# psu_board.net
KiCad netlist of a schematic drawn in EAGLE
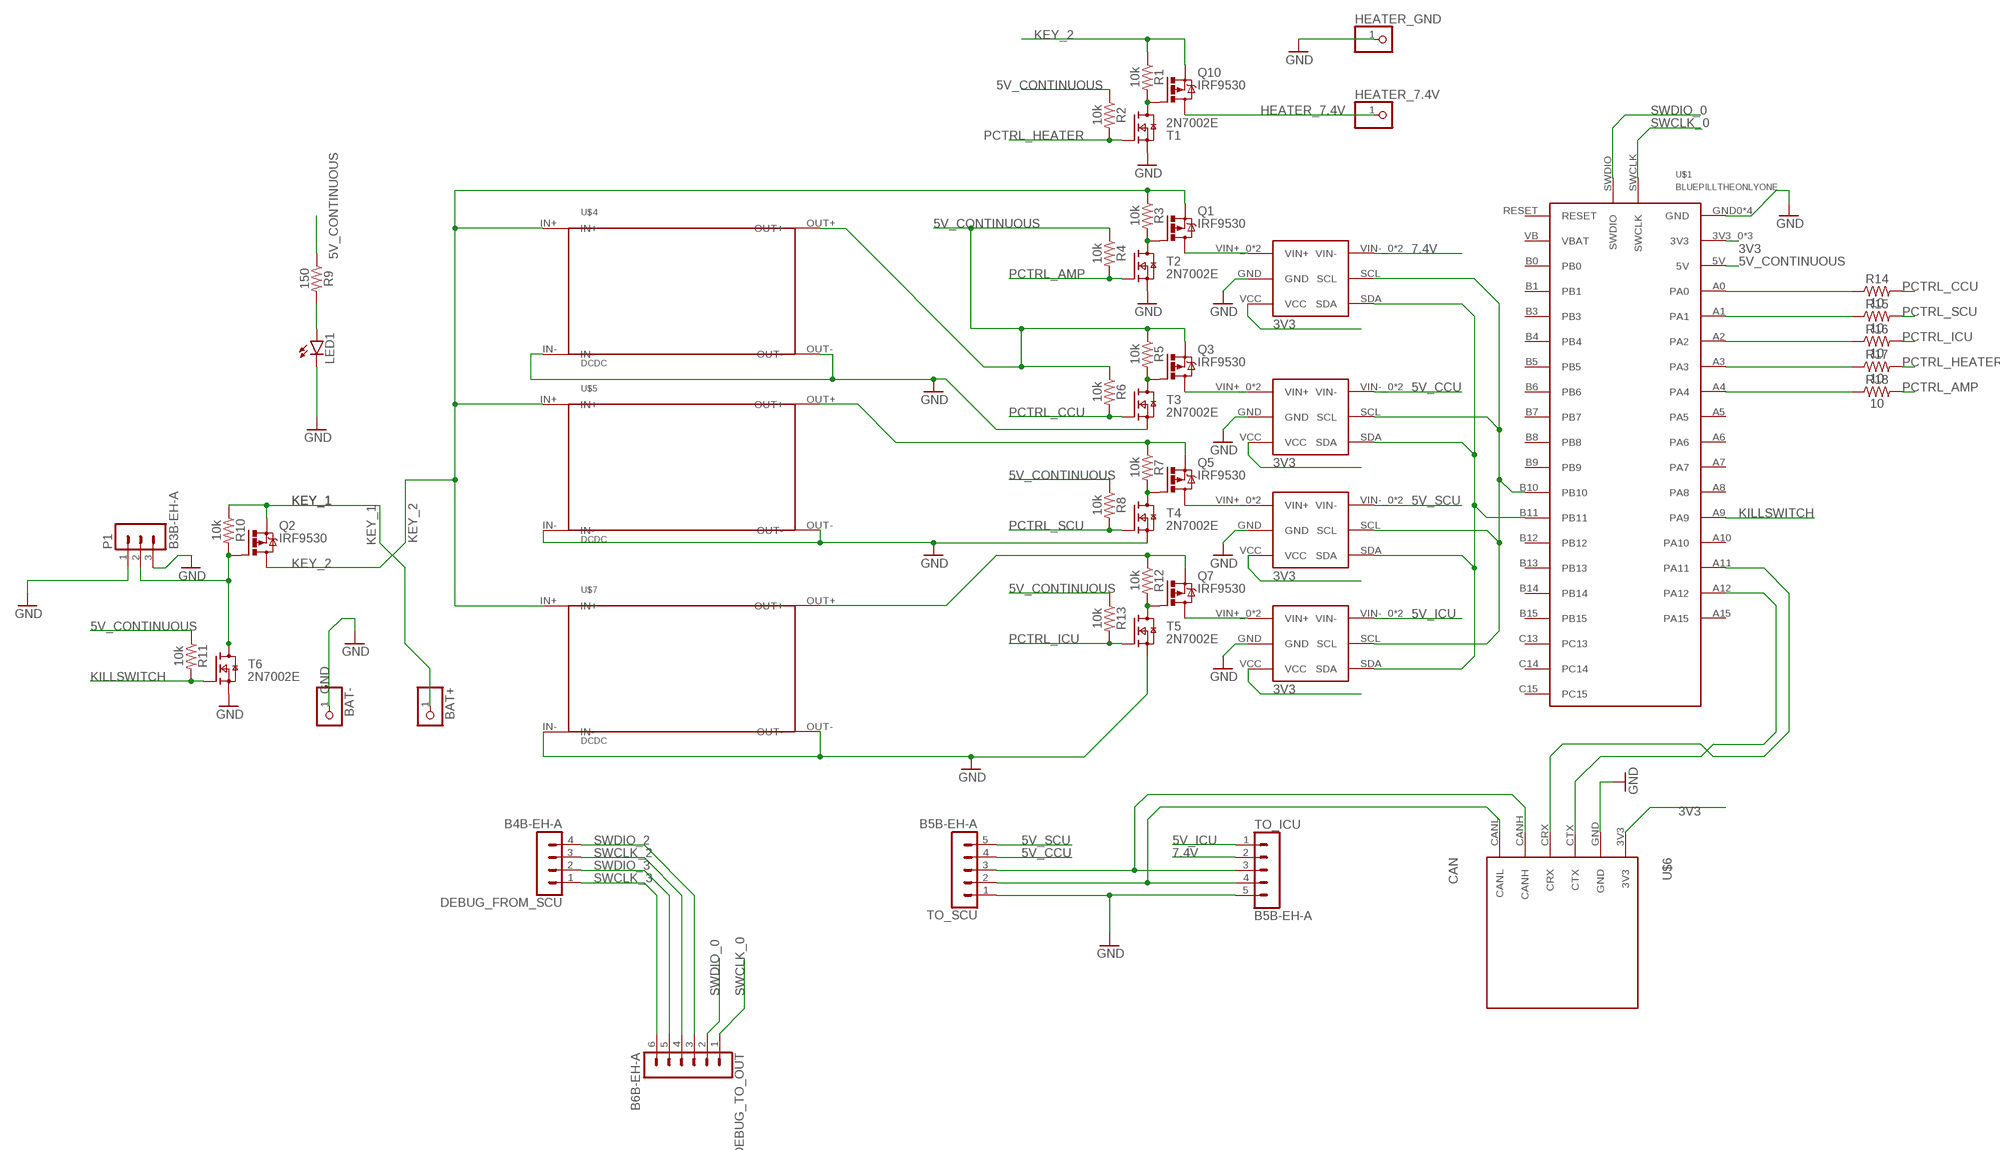
[diagram p0: schematic, sheet 1]

(export (version "E")
  (design (tool "Eeschema 10.0.6"))
  (components
    (comp (ref "BAT+")
      (value "PINHD-1X1")
      (footprint "eagle-import:1X01")
      (libsource (lib "eagle-import") (part "PINHD-1X1"))
    )
    (comp (ref "BAT-")
      (value "PINHD-1X1")
      (footprint "eagle-import:1X01")
      (libsource (lib "eagle-import") (part "PINHD-1X1"))
    )
    (comp (ref "DEBUG_FROM_SCU")
      (value "B4B-EH-A")
      (footprint "eagle-import:B4B-EH-A")
      (libsource (lib "eagle-import") (part "B4B-EH-A"))
    )
    (comp (ref "DEBUG_TO_OUT")
      (value "B6B-EH-A")
      (footprint "eagle-import:B6B-EH-A")
      (libsource (lib "eagle-import") (part "B6B-EH-A"))
    )
    (comp (ref "HEATER_7.4V")
      (value "PINHD-1X1")
      (footprint "eagle-import:1X01")
      (libsource (lib "eagle-import") (part "PINHD-1X1"))
    )
    (comp (ref "HEATER_GND")
      (value "PINHD-1X1")
      (footprint "eagle-import:1X01")
      (libsource (lib "eagle-import") (part "PINHD-1X1"))
    )
    (comp (ref "LED1")
      (value "LED5MM")
      (footprint "eagle-import:LED5MM")
      (libsource (lib "eagle-import") (part "LED5MM"))
    )
    (comp (ref "P1")
      (value "B3B-EH-A")
      (footprint "eagle-import:B3B-EH-A")
      (libsource (lib "eagle-import") (part "B3B-EH-A"))
    )
    (comp (ref "Q1")
      (value "IRF9530")
      (footprint "eagle-import:TO220BV")
      (libsource (lib "eagle-import") (part "IRF9530"))
    )
    (comp (ref "Q2")
      (value "IRF9530")
      (footprint "eagle-import:TO220BV")
      (libsource (lib "eagle-import") (part "IRF9530"))
    )
    (comp (ref "Q3")
      (value "IRF9530")
      (footprint "eagle-import:TO220BV")
      (libsource (lib "eagle-import") (part "IRF9530"))
    )
    (comp (ref "Q5")
      (value "IRF9530")
      (footprint "eagle-import:TO220BV")
      (libsource (lib "eagle-import") (part "IRF9530"))
    )
    (comp (ref "Q7")
      (value "IRF9530")
      (footprint "eagle-import:TO220BV")
      (libsource (lib "eagle-import") (part "IRF9530"))
    )
    (comp (ref "Q10")
      (value "IRF9530")
      (footprint "eagle-import:TO220BV")
      (libsource (lib "eagle-import") (part "IRF9530"))
    )
    (comp (ref "R1")
      (value "10k")
      (footprint "eagle-import:AXIAL-0.3")
      (libsource (lib "eagle-import") (part "RESISTORAXIAL-0.3"))
    )
    (comp (ref "R2")
      (value "10k")
      (footprint "eagle-import:AXIAL-0.3")
      (libsource (lib "eagle-import") (part "RESISTORAXIAL-0.3"))
    )
    (comp (ref "R3")
      (value "10k")
      (footprint "eagle-import:AXIAL-0.3")
      (libsource (lib "eagle-import") (part "RESISTORAXIAL-0.3"))
    )
    (comp (ref "R4")
      (value "10k")
      (footprint "eagle-import:AXIAL-0.3")
      (libsource (lib "eagle-import") (part "RESISTORAXIAL-0.3"))
    )
    (comp (ref "R5")
      (value "10k")
      (footprint "eagle-import:AXIAL-0.3")
      (libsource (lib "eagle-import") (part "RESISTORAXIAL-0.3"))
    )
    (comp (ref "R6")
      (value "10k")
      (footprint "eagle-import:AXIAL-0.3")
      (libsource (lib "eagle-import") (part "RESISTORAXIAL-0.3"))
    )
    (comp (ref "R7")
      (value "10k")
      (footprint "eagle-import:AXIAL-0.3")
      (libsource (lib "eagle-import") (part "RESISTORAXIAL-0.3"))
    )
    (comp (ref "R8")
      (value "10k")
      (footprint "eagle-import:AXIAL-0.3")
      (libsource (lib "eagle-import") (part "RESISTORAXIAL-0.3"))
    )
    (comp (ref "R9")
      (value "150")
      (footprint "eagle-import:AXIAL-0.3")
      (libsource (lib "eagle-import") (part "RESISTORAXIAL-0.3"))
    )
    (comp (ref "R10")
      (value "10k")
      (footprint "eagle-import:AXIAL-0.3")
      (libsource (lib "eagle-import") (part "RESISTORAXIAL-0.3"))
    )
    (comp (ref "R11")
      (value "10k")
      (footprint "eagle-import:AXIAL-0.3")
      (libsource (lib "eagle-import") (part "RESISTORAXIAL-0.3"))
    )
    (comp (ref "R12")
      (value "10k")
      (footprint "eagle-import:AXIAL-0.3")
      (libsource (lib "eagle-import") (part "RESISTORAXIAL-0.3"))
    )
    (comp (ref "R13")
      (value "10k")
      (footprint "eagle-import:AXIAL-0.3")
      (libsource (lib "eagle-import") (part "RESISTORAXIAL-0.3"))
    )
    (comp (ref "R14")
      (value "10")
      (footprint "eagle-import:AXIAL-0.3")
      (libsource (lib "eagle-import") (part "RESISTORAXIAL-0.3"))
    )
    (comp (ref "R15")
      (value "10")
      (footprint "eagle-import:AXIAL-0.3")
      (libsource (lib "eagle-import") (part "RESISTORAXIAL-0.3"))
    )
    (comp (ref "R16")
      (value "10")
      (footprint "eagle-import:AXIAL-0.3")
      (libsource (lib "eagle-import") (part "RESISTORAXIAL-0.3"))
    )
    (comp (ref "R17")
      (value "10")
      (footprint "eagle-import:AXIAL-0.3")
      (libsource (lib "eagle-import") (part "RESISTORAXIAL-0.3"))
    )
    (comp (ref "R18")
      (value "10")
      (footprint "eagle-import:AXIAL-0.3")
      (libsource (lib "eagle-import") (part "RESISTORAXIAL-0.3"))
    )
    (comp (ref "T1")
      (value "2N7002E")
      (footprint "eagle-import:SOT23")
      (libsource (lib "eagle-import") (part "2N7002E"))
    )
    (comp (ref "T2")
      (value "2N7002E")
      (footprint "eagle-import:SOT23")
      (libsource (lib "eagle-import") (part "2N7002E"))
    )
    (comp (ref "T3")
      (value "2N7002E")
      (footprint "eagle-import:SOT23")
      (libsource (lib "eagle-import") (part "2N7002E"))
    )
    (comp (ref "T4")
      (value "2N7002E")
      (footprint "eagle-import:SOT23")
      (libsource (lib "eagle-import") (part "2N7002E"))
    )
    (comp (ref "T5")
      (value "2N7002E")
      (footprint "eagle-import:SOT23")
      (libsource (lib "eagle-import") (part "2N7002E"))
    )
    (comp (ref "T6")
      (value "2N7002E")
      (footprint "eagle-import:SOT23")
      (libsource (lib "eagle-import") (part "2N7002E"))
    )
    (comp (ref "TO_ICU")
      (value "B5B-EH-A")
      (footprint "eagle-import:B5B-EH-A")
      (libsource (lib "eagle-import") (part "B5B-EH-A"))
    )
    (comp (ref "TO_SCU")
      (value "B5B-EH-A")
      (footprint "eagle-import:B5B-EH-A")
      (libsource (lib "eagle-import") (part "B5B-EH-A"))
    )
    (comp (ref "U$1")
      (value "BLUEPILLTHEONLYONE")
      (footprint "eagle-import:BLUEPIL")
      (libsource (lib "eagle-import") (part "BLUEPILLTHEONLYONE"))
    )
    (comp (ref "U$2")
      (value "INA")
      (footprint "eagle-import:INA")
      (libsource (lib "eagle-import") (part "INA"))
    )
    (comp (ref "U$3")
      (value "INA")
      (footprint "eagle-import:INA")
      (libsource (lib "eagle-import") (part "INA"))
    )
    (comp (ref "U$4")
      (value "DCDC")
      (footprint "eagle-import:DCDC")
      (libsource (lib "eagle-import") (part "DCDC"))
    )
    (comp (ref "U$5")
      (value "DCDC")
      (footprint "eagle-import:DCDC")
      (libsource (lib "eagle-import") (part "DCDC"))
    )
    (comp (ref "U$6")
      (value "CAN")
      (footprint "eagle-import:CAN")
      (libsource (lib "eagle-import") (part "CAN"))
    )
    (comp (ref "U$7")
      (value "DCDC")
      (footprint "eagle-import:DCDC")
      (libsource (lib "eagle-import") (part "DCDC"))
    )
    (comp (ref "U$8")
      (value "INA")
      (footprint "eagle-import:INA")
      (libsource (lib "eagle-import") (part "INA"))
    )
    (comp (ref "U$9")
      (value "INA")
      (footprint "eagle-import:INA")
      (libsource (lib "eagle-import") (part "INA"))
    )
  )
  (nets
    (net (code "1") (name "/3V3") (class "Default")
      (node (ref "U$1") (pin "3V3_0") (pinfunction "3V3_3V3_0") (pintype "bidirectional"))
      (node (ref "U$1") (pin "3V3_1") (pinfunction "3V3_3V3_1") (pintype "bidirectional"))
      (node (ref "U$1") (pin "3V3_2") (pinfunction "3V3_3V3_2") (pintype "bidirectional"))
      (node (ref "U$2") (pin "VCC") (pinfunction "VCC_VCC") (pintype "bidirectional"))
      (node (ref "U$3") (pin "VCC") (pinfunction "VCC_VCC") (pintype "bidirectional"))
      (node (ref "U$6") (pin "3V3") (pinfunction "3V3_3V3") (pintype "bidirectional"))
      (node (ref "U$8") (pin "VCC") (pinfunction "VCC_VCC") (pintype "bidirectional"))
      (node (ref "U$9") (pin "VCC") (pinfunction "VCC_VCC") (pintype "bidirectional"))
    )
    (net (code "2") (name "/5V_CCU") (class "Default")
      (node (ref "TO_SCU") (pin "4") (pinfunction "4_4") (pintype "passive"))
      (node (ref "U$9") (pin "VIN-_0") (pinfunction "VIN-_VIN-_0") (pintype "bidirectional"))
      (node (ref "U$9") (pin "VIN-_1") (pinfunction "VIN-_VIN-_1") (pintype "bidirectional"))
    )
    (net (code "3") (name "/5V_CONTINUOUS") (class "Default")
      (node (ref "Q3") (pin "S") (pinfunction "S_S") (pintype "passive"))
      (node (ref "R11") (pin "P$1") (pinfunction "1_P$1") (pintype "passive"))
      (node (ref "R13") (pin "P$1") (pinfunction "1_P$1") (pintype "passive"))
      (node (ref "R2") (pin "P$1") (pinfunction "1_P$1") (pintype "passive"))
      (node (ref "R4") (pin "P$1") (pinfunction "1_P$1") (pintype "passive"))
      (node (ref "R5") (pin "P$1") (pinfunction "1_P$1") (pintype "passive"))
      (node (ref "R6") (pin "P$1") (pinfunction "1_P$1") (pintype "passive"))
      (node (ref "R8") (pin "P$1") (pinfunction "1_P$1") (pintype "passive"))
      (node (ref "R9") (pin "P$1") (pinfunction "1_P$1") (pintype "passive"))
      (node (ref "U$1") (pin "5V") (pinfunction "5V_5V") (pintype "bidirectional"))
      (node (ref "U$4") (pin "OUT+") (pinfunction "OUT+_OUT+") (pintype "bidirectional"))
    )
    (net (code "4") (name "/5V_ICU") (class "Default")
      (node (ref "TO_ICU") (pin "1") (pinfunction "1_1") (pintype "passive"))
      (node (ref "U$2") (pin "VIN-_0") (pinfunction "VIN-_VIN-_0") (pintype "bidirectional"))
      (node (ref "U$2") (pin "VIN-_1") (pinfunction "VIN-_VIN-_1") (pintype "bidirectional"))
    )
    (net (code "5") (name "/5V_SCU") (class "Default")
      (node (ref "TO_SCU") (pin "5") (pinfunction "5_5") (pintype "passive"))
      (node (ref "U$8") (pin "VIN-_0") (pinfunction "VIN-_VIN-_0") (pintype "bidirectional"))
      (node (ref "U$8") (pin "VIN-_1") (pinfunction "VIN-_VIN-_1") (pintype "bidirectional"))
    )
    (net (code "6") (name "/7.4V") (class "Default")
      (node (ref "TO_ICU") (pin "2") (pinfunction "2_2") (pintype "passive"))
      (node (ref "U$3") (pin "VIN-_0") (pinfunction "VIN-_VIN-_0") (pintype "bidirectional"))
      (node (ref "U$3") (pin "VIN-_1") (pinfunction "VIN-_VIN-_1") (pintype "bidirectional"))
    )
    (net (code "7") (name "/HEATER_7.4V") (class "Default")
      (node (ref "HEATER_7.4V") (pin "1") (pinfunction "1_1") (pintype "passive"))
      (node (ref "Q10") (pin "D") (pinfunction "D_D") (pintype "passive"))
    )
    (net (code "8") (name "/KEY_1") (class "Default")
      (node (ref "BAT+") (pin "1") (pinfunction "1_1") (pintype "passive"))
      (node (ref "Q2") (pin "S") (pinfunction "S_S") (pintype "passive"))
      (node (ref "R10") (pin "P$1") (pinfunction "1_P$1") (pintype "passive"))
    )
    (net (code "9") (name "/KEY_2") (class "Default")
      (node (ref "Q1") (pin "S") (pinfunction "S_S") (pintype "passive"))
      (node (ref "Q10") (pin "S") (pinfunction "S_S") (pintype "passive"))
      (node (ref "Q2") (pin "D") (pinfunction "D_D") (pintype "passive"))
      (node (ref "R1") (pin "P$1") (pinfunction "1_P$1") (pintype "passive"))
      (node (ref "R3") (pin "P$1") (pinfunction "1_P$1") (pintype "passive"))
      (node (ref "U$4") (pin "IN+") (pinfunction "IN+_IN+") (pintype "bidirectional"))
      (node (ref "U$5") (pin "IN+") (pinfunction "IN+_IN+") (pintype "bidirectional"))
      (node (ref "U$7") (pin "IN+") (pinfunction "IN+_IN+") (pintype "bidirectional"))
    )
    (net (code "10") (name "/KILLSWITCH") (class "Default")
      (node (ref "R11") (pin "P$2") (pinfunction "2_P$2") (pintype "passive"))
      (node (ref "T6") (pin "1") (pinfunction "G_1") (pintype "passive"))
      (node (ref "U$1") (pin "A9") (pinfunction "PA9_A9") (pintype "bidirectional"))
    )
    (net (code "11") (name "/PCTRL_AMP") (class "Default")
      (node (ref "R18") (pin "P$2") (pinfunction "2_P$2") (pintype "passive"))
      (node (ref "R4") (pin "P$2") (pinfunction "2_P$2") (pintype "passive"))
      (node (ref "T2") (pin "1") (pinfunction "G_1") (pintype "passive"))
    )
    (net (code "12") (name "/PCTRL_CCU") (class "Default")
      (node (ref "R14") (pin "P$2") (pinfunction "2_P$2") (pintype "passive"))
      (node (ref "R6") (pin "P$2") (pinfunction "2_P$2") (pintype "passive"))
      (node (ref "T3") (pin "1") (pinfunction "G_1") (pintype "passive"))
    )
    (net (code "13") (name "/PCTRL_HEATER") (class "Default")
      (node (ref "R17") (pin "P$2") (pinfunction "2_P$2") (pintype "passive"))
      (node (ref "R2") (pin "P$2") (pinfunction "2_P$2") (pintype "passive"))
      (node (ref "T1") (pin "1") (pinfunction "G_1") (pintype "passive"))
    )
    (net (code "14") (name "/PCTRL_ICU") (class "Default")
      (node (ref "R13") (pin "P$2") (pinfunction "2_P$2") (pintype "passive"))
      (node (ref "R16") (pin "P$2") (pinfunction "2_P$2") (pintype "passive"))
      (node (ref "T5") (pin "1") (pinfunction "G_1") (pintype "passive"))
    )
    (net (code "15") (name "/PCTRL_SCU") (class "Default")
      (node (ref "R15") (pin "P$2") (pinfunction "2_P$2") (pintype "passive"))
      (node (ref "R8") (pin "P$2") (pinfunction "2_P$2") (pintype "passive"))
      (node (ref "T4") (pin "1") (pinfunction "G_1") (pintype "passive"))
    )
    (net (code "16") (name "/SWCLK_0") (class "Default")
      (node (ref "DEBUG_TO_OUT") (pin "1") (pinfunction "1_1") (pintype "passive"))
      (node (ref "U$1") (pin "SWCLK") (pinfunction "SWCLK_SWCLK") (pintype "bidirectional"))
    )
    (net (code "17") (name "/SWCLK_2") (class "Default")
      (node (ref "DEBUG_FROM_SCU") (pin "3") (pinfunction "3_3") (pintype "passive"))
      (node (ref "DEBUG_TO_OUT") (pin "4") (pinfunction "4_4") (pintype "passive"))
    )
    (net (code "18") (name "/SWCLK_3") (class "Default")
      (node (ref "DEBUG_FROM_SCU") (pin "1") (pinfunction "1_1") (pintype "passive"))
      (node (ref "DEBUG_TO_OUT") (pin "6") (pinfunction "6_6") (pintype "passive"))
    )
    (net (code "19") (name "/SWDIO_0") (class "Default")
      (node (ref "DEBUG_TO_OUT") (pin "2") (pinfunction "2_2") (pintype "passive"))
      (node (ref "U$1") (pin "SWDIO") (pinfunction "SWDIO_SWDIO") (pintype "bidirectional"))
    )
    (net (code "20") (name "/SWDIO_2") (class "Default")
      (node (ref "DEBUG_FROM_SCU") (pin "4") (pinfunction "4_4") (pintype "passive"))
      (node (ref "DEBUG_TO_OUT") (pin "3") (pinfunction "3_3") (pintype "passive"))
    )
    (net (code "21") (name "/SWDIO_3") (class "Default")
      (node (ref "DEBUG_FROM_SCU") (pin "2") (pinfunction "2_2") (pintype "passive"))
      (node (ref "DEBUG_TO_OUT") (pin "5") (pinfunction "5_5") (pintype "passive"))
    )
    (net (code "22") (name "GND") (class "Default")
      (node (ref "BAT-") (pin "1") (pinfunction "1_1") (pintype "passive"))
      (node (ref "HEATER_GND") (pin "1") (pinfunction "1_1") (pintype "passive"))
      (node (ref "LED1") (pin "K") (pinfunction "C_K") (pintype "passive"))
      (node (ref "P1") (pin "1") (pinfunction "1_1") (pintype "passive"))
      (node (ref "P1") (pin "3") (pinfunction "3_3") (pintype "passive"))
      (node (ref "T1") (pin "2") (pinfunction "S_2") (pintype "passive"))
      (node (ref "T2") (pin "2") (pinfunction "S_2") (pintype "passive"))
      (node (ref "T3") (pin "2") (pinfunction "S_2") (pintype "passive"))
      (node (ref "T4") (pin "2") (pinfunction "S_2") (pintype "passive"))
      (node (ref "T5") (pin "2") (pinfunction "S_2") (pintype "passive"))
      (node (ref "T6") (pin "2") (pinfunction "S_2") (pintype "passive"))
      (node (ref "TO_ICU") (pin "5") (pinfunction "5_5") (pintype "passive"))
      (node (ref "TO_SCU") (pin "1") (pinfunction "1_1") (pintype "passive"))
      (node (ref "U$1") (pin "GND0") (pinfunction "GND_GND0") (pintype "bidirectional"))
      (node (ref "U$1") (pin "GND1") (pinfunction "GND_GND1") (pintype "bidirectional"))
      (node (ref "U$1") (pin "GND2") (pinfunction "GND_GND2") (pintype "bidirectional"))
      (node (ref "U$1") (pin "GND3") (pinfunction "GND_GND3") (pintype "bidirectional"))
      (node (ref "U$2") (pin "GND") (pinfunction "GND_GND") (pintype "bidirectional"))
      (node (ref "U$3") (pin "GND") (pinfunction "GND_GND") (pintype "bidirectional"))
      (node (ref "U$4") (pin "IN-") (pinfunction "IN-_IN-") (pintype "bidirectional"))
      (node (ref "U$4") (pin "OUT-") (pinfunction "OUT-_OUT-") (pintype "bidirectional"))
      (node (ref "U$5") (pin "IN-") (pinfunction "IN-_IN-") (pintype "bidirectional"))
      (node (ref "U$5") (pin "OUT-") (pinfunction "OUT-_OUT-") (pintype "bidirectional"))
      (node (ref "U$6") (pin "GND") (pinfunction "GND_GND") (pintype "bidirectional"))
      (node (ref "U$7") (pin "IN-") (pinfunction "IN-_IN-") (pintype "bidirectional"))
      (node (ref "U$7") (pin "OUT-") (pinfunction "OUT-_OUT-") (pintype "bidirectional"))
      (node (ref "U$8") (pin "GND") (pinfunction "GND_GND") (pintype "bidirectional"))
      (node (ref "U$9") (pin "GND") (pinfunction "GND_GND") (pintype "bidirectional"))
    )
    (net (code "23") (name "Net-(Q1-PadD)") (class "Default")
      (node (ref "Q1") (pin "D") (pinfunction "D_D") (pintype "passive"))
      (node (ref "U$3") (pin "VIN+_0") (pinfunction "VIN+_VIN+_0") (pintype "bidirectional"))
      (node (ref "U$3") (pin "VIN+_1") (pinfunction "VIN+_VIN+_1") (pintype "bidirectional"))
    )
    (net (code "24") (name "Net-(Q3-PadD)") (class "Default")
      (node (ref "Q3") (pin "D") (pinfunction "D_D") (pintype "passive"))
      (node (ref "U$9") (pin "VIN+_0") (pinfunction "VIN+_VIN+_0") (pintype "bidirectional"))
      (node (ref "U$9") (pin "VIN+_1") (pinfunction "VIN+_VIN+_1") (pintype "bidirectional"))
    )
    (net (code "25") (name "Net-(Q5-PadD)") (class "Default")
      (node (ref "Q5") (pin "D") (pinfunction "D_D") (pintype "passive"))
      (node (ref "U$8") (pin "VIN+_0") (pinfunction "VIN+_VIN+_0") (pintype "bidirectional"))
      (node (ref "U$8") (pin "VIN+_1") (pinfunction "VIN+_VIN+_1") (pintype "bidirectional"))
    )
    (net (code "26") (name "Net-(Q7-PadD)") (class "Default")
      (node (ref "Q7") (pin "D") (pinfunction "D_D") (pintype "passive"))
      (node (ref "U$2") (pin "VIN+_0") (pinfunction "VIN+_VIN+_0") (pintype "bidirectional"))
      (node (ref "U$2") (pin "VIN+_1") (pinfunction "VIN+_VIN+_1") (pintype "bidirectional"))
    )
    (net (code "27") (name "Net-(R1-2)") (class "Default")
      (node (ref "Q10") (pin "G") (pinfunction "G_G") (pintype "passive"))
      (node (ref "R1") (pin "P$2") (pinfunction "2_P$2") (pintype "passive"))
      (node (ref "T1") (pin "3") (pinfunction "D_3") (pintype "passive"))
    )
    (net (code "28") (name "Net-(R3-2)") (class "Default")
      (node (ref "Q1") (pin "G") (pinfunction "G_G") (pintype "passive"))
      (node (ref "R3") (pin "P$2") (pinfunction "2_P$2") (pintype "passive"))
      (node (ref "T2") (pin "3") (pinfunction "D_3") (pintype "passive"))
    )
    (net (code "29") (name "Net-(R5-2)") (class "Default")
      (node (ref "Q3") (pin "G") (pinfunction "G_G") (pintype "passive"))
      (node (ref "R5") (pin "P$2") (pinfunction "2_P$2") (pintype "passive"))
      (node (ref "T3") (pin "3") (pinfunction "D_3") (pintype "passive"))
    )
    (net (code "30") (name "Net-(R7-1)") (class "Default")
      (node (ref "Q5") (pin "S") (pinfunction "S_S") (pintype "passive"))
      (node (ref "R7") (pin "P$1") (pinfunction "1_P$1") (pintype "passive"))
      (node (ref "U$5") (pin "OUT+") (pinfunction "OUT+_OUT+") (pintype "bidirectional"))
    )
    (net (code "31") (name "Net-(R7-2)") (class "Default")
      (node (ref "Q5") (pin "G") (pinfunction "G_G") (pintype "passive"))
      (node (ref "R7") (pin "P$2") (pinfunction "2_P$2") (pintype "passive"))
      (node (ref "T4") (pin "3") (pinfunction "D_3") (pintype "passive"))
    )
    (net (code "32") (name "Net-(R9-2)") (class "Default")
      (node (ref "LED1") (pin "A") (pinfunction "A_A") (pintype "passive"))
      (node (ref "R9") (pin "P$2") (pinfunction "2_P$2") (pintype "passive"))
    )
    (net (code "33") (name "Net-(R10-2)") (class "Default")
      (node (ref "P1") (pin "2") (pinfunction "2_2") (pintype "passive"))
      (node (ref "Q2") (pin "G") (pinfunction "G_G") (pintype "passive"))
      (node (ref "R10") (pin "P$2") (pinfunction "2_P$2") (pintype "passive"))
      (node (ref "T6") (pin "3") (pinfunction "D_3") (pintype "passive"))
    )
    (net (code "34") (name "Net-(R12-1)") (class "Default")
      (node (ref "Q7") (pin "S") (pinfunction "S_S") (pintype "passive"))
      (node (ref "R12") (pin "P$1") (pinfunction "1_P$1") (pintype "passive"))
      (node (ref "U$7") (pin "OUT+") (pinfunction "OUT+_OUT+") (pintype "bidirectional"))
    )
    (net (code "35") (name "Net-(R12-2)") (class "Default")
      (node (ref "Q7") (pin "G") (pinfunction "G_G") (pintype "passive"))
      (node (ref "R12") (pin "P$2") (pinfunction "2_P$2") (pintype "passive"))
      (node (ref "T5") (pin "3") (pinfunction "D_3") (pintype "passive"))
    )
    (net (code "36") (name "Net-(R14-1)") (class "Default")
      (node (ref "R14") (pin "P$1") (pinfunction "1_P$1") (pintype "passive"))
      (node (ref "U$1") (pin "A0") (pinfunction "PA0_A0") (pintype "bidirectional"))
    )
    (net (code "37") (name "Net-(R15-1)") (class "Default")
      (node (ref "R15") (pin "P$1") (pinfunction "1_P$1") (pintype "passive"))
      (node (ref "U$1") (pin "A1") (pinfunction "PA1_A1") (pintype "bidirectional"))
    )
    (net (code "38") (name "Net-(R16-1)") (class "Default")
      (node (ref "R16") (pin "P$1") (pinfunction "1_P$1") (pintype "passive"))
      (node (ref "U$1") (pin "A2") (pinfunction "PA2_A2") (pintype "bidirectional"))
    )
    (net (code "39") (name "Net-(R17-1)") (class "Default")
      (node (ref "R17") (pin "P$1") (pinfunction "1_P$1") (pintype "passive"))
      (node (ref "U$1") (pin "A3") (pinfunction "PA3_A3") (pintype "bidirectional"))
    )
    (net (code "40") (name "Net-(R18-1)") (class "Default")
      (node (ref "R18") (pin "P$1") (pinfunction "1_P$1") (pintype "passive"))
      (node (ref "U$1") (pin "A4") (pinfunction "PA4_A4") (pintype "bidirectional"))
    )
    (net (code "41") (name "Net-(TO_ICU-Pad3)") (class "Default")
      (node (ref "TO_ICU") (pin "3") (pinfunction "3_3") (pintype "passive"))
      (node (ref "TO_SCU") (pin "3") (pinfunction "3_3") (pintype "passive"))
      (node (ref "U$6") (pin "CANH") (pinfunction "CANH_CANH") (pintype "bidirectional"))
    )
    (net (code "42") (name "Net-(TO_ICU-Pad4)") (class "Default")
      (node (ref "TO_ICU") (pin "4") (pinfunction "4_4") (pintype "passive"))
      (node (ref "TO_SCU") (pin "2") (pinfunction "2_2") (pintype "passive"))
      (node (ref "U$6") (pin "CANL") (pinfunction "CANL_CANL") (pintype "bidirectional"))
    )
    (net (code "43") (name "Net-(U$1-PA11)") (class "Default")
      (node (ref "U$1") (pin "A11") (pinfunction "PA11_A11") (pintype "bidirectional"))
      (node (ref "U$6") (pin "CRX") (pinfunction "CRX_CRX") (pintype "bidirectional"))
    )
    (net (code "44") (name "Net-(U$1-PA12)") (class "Default")
      (node (ref "U$1") (pin "A12") (pinfunction "PA12_A12") (pintype "bidirectional"))
      (node (ref "U$6") (pin "CTX") (pinfunction "CTX_CTX") (pintype "bidirectional"))
    )
    (net (code "45") (name "Net-(U$1-PB10)") (class "Default")
      (node (ref "U$1") (pin "B10") (pinfunction "PB10_B10") (pintype "bidirectional"))
      (node (ref "U$2") (pin "SCL") (pinfunction "SCL_SCL") (pintype "bidirectional"))
      (node (ref "U$3") (pin "SCL") (pinfunction "SCL_SCL") (pintype "bidirectional"))
      (node (ref "U$8") (pin "SCL") (pinfunction "SCL_SCL") (pintype "bidirectional"))
      (node (ref "U$9") (pin "SCL") (pinfunction "SCL_SCL") (pintype "bidirectional"))
    )
    (net (code "46") (name "Net-(U$1-PB11)") (class "Default")
      (node (ref "U$1") (pin "B11") (pinfunction "PB11_B11") (pintype "bidirectional"))
      (node (ref "U$2") (pin "SDA") (pinfunction "SDA_SDA") (pintype "bidirectional"))
      (node (ref "U$3") (pin "SDA") (pinfunction "SDA_SDA") (pintype "bidirectional"))
      (node (ref "U$8") (pin "SDA") (pinfunction "SDA_SDA") (pintype "bidirectional"))
      (node (ref "U$9") (pin "SDA") (pinfunction "SDA_SDA") (pintype "bidirectional"))
    )
    (net (code "47") (name "unconnected-(U$1-PA5-PadA5)") (class "Default")
      (node (ref "U$1") (pin "A5") (pinfunction "PA5_A5") (pintype "bidirectional"))
    )
    (net (code "48") (name "unconnected-(U$1-PA6-PadA6)") (class "Default")
      (node (ref "U$1") (pin "A6") (pinfunction "PA6_A6") (pintype "bidirectional"))
    )
    (net (code "49") (name "unconnected-(U$1-PA7-PadA7)") (class "Default")
      (node (ref "U$1") (pin "A7") (pinfunction "PA7_A7") (pintype "bidirectional"))
    )
    (net (code "50") (name "unconnected-(U$1-PA8-PadA8)") (class "Default")
      (node (ref "U$1") (pin "A8") (pinfunction "PA8_A8") (pintype "bidirectional"))
    )
    (net (code "51") (name "unconnected-(U$1-PA10-PadA10)") (class "Default")
      (node (ref "U$1") (pin "A10") (pinfunction "PA10_A10") (pintype "bidirectional"))
    )
    (net (code "52") (name "unconnected-(U$1-PA15-PadA15)") (class "Default")
      (node (ref "U$1") (pin "A15") (pinfunction "PA15_A15") (pintype "bidirectional"))
    )
    (net (code "53") (name "unconnected-(U$1-PB0-PadB0)") (class "Default")
      (node (ref "U$1") (pin "B0") (pinfunction "PB0_B0") (pintype "bidirectional"))
    )
    (net (code "54") (name "unconnected-(U$1-PB1-PadB1)") (class "Default")
      (node (ref "U$1") (pin "B1") (pinfunction "PB1_B1") (pintype "bidirectional"))
    )
    (net (code "55") (name "unconnected-(U$1-PB3-PadB3)") (class "Default")
      (node (ref "U$1") (pin "B3") (pinfunction "PB3_B3") (pintype "bidirectional"))
    )
    (net (code "56") (name "unconnected-(U$1-PB4-PadB4)") (class "Default")
      (node (ref "U$1") (pin "B4") (pinfunction "PB4_B4") (pintype "bidirectional"))
    )
    (net (code "57") (name "unconnected-(U$1-PB5-PadB5)") (class "Default")
      (node (ref "U$1") (pin "B5") (pinfunction "PB5_B5") (pintype "bidirectional"))
    )
    (net (code "58") (name "unconnected-(U$1-PB6-PadB6)") (class "Default")
      (node (ref "U$1") (pin "B6") (pinfunction "PB6_B6") (pintype "bidirectional"))
    )
    (net (code "59") (name "unconnected-(U$1-PB7-PadB7)") (class "Default")
      (node (ref "U$1") (pin "B7") (pinfunction "PB7_B7") (pintype "bidirectional"))
    )
    (net (code "60") (name "unconnected-(U$1-PB8-PadB8)") (class "Default")
      (node (ref "U$1") (pin "B8") (pinfunction "PB8_B8") (pintype "bidirectional"))
    )
    (net (code "61") (name "unconnected-(U$1-PB9-PadB9)") (class "Default")
      (node (ref "U$1") (pin "B9") (pinfunction "PB9_B9") (pintype "bidirectional"))
    )
    (net (code "62") (name "unconnected-(U$1-PB12-PadB12)") (class "Default")
      (node (ref "U$1") (pin "B12") (pinfunction "PB12_B12") (pintype "bidirectional"))
    )
    (net (code "63") (name "unconnected-(U$1-PB13-PadB13)") (class "Default")
      (node (ref "U$1") (pin "B13") (pinfunction "PB13_B13") (pintype "bidirectional"))
    )
    (net (code "64") (name "unconnected-(U$1-PB14-PadB14)") (class "Default")
      (node (ref "U$1") (pin "B14") (pinfunction "PB14_B14") (pintype "bidirectional"))
    )
    (net (code "65") (name "unconnected-(U$1-PB15-PadB15)") (class "Default")
      (node (ref "U$1") (pin "B15") (pinfunction "PB15_B15") (pintype "bidirectional"))
    )
    (net (code "66") (name "unconnected-(U$1-PC13-PadC13)") (class "Default")
      (node (ref "U$1") (pin "C13") (pinfunction "PC13_C13") (pintype "bidirectional"))
    )
    (net (code "67") (name "unconnected-(U$1-PC14-PadC14)") (class "Default")
      (node (ref "U$1") (pin "C14") (pinfunction "PC14_C14") (pintype "bidirectional"))
    )
    (net (code "68") (name "unconnected-(U$1-PC15-PadC15)") (class "Default")
      (node (ref "U$1") (pin "C15") (pinfunction "PC15_C15") (pintype "bidirectional"))
    )
    (net (code "69") (name "unconnected-(U$1-PadRESET)") (class "Default")
      (node (ref "U$1") (pin "RESET") (pinfunction "RESET_RESET") (pintype "bidirectional"))
    )
    (net (code "70") (name "unconnected-(U$1-VBAT-PadVB)") (class "Default")
      (node (ref "U$1") (pin "VB") (pinfunction "VBAT_VB") (pintype "bidirectional"))
    )
  )
)
